# design.net
KiCad netlist of a schematic drawn in Altium Designer
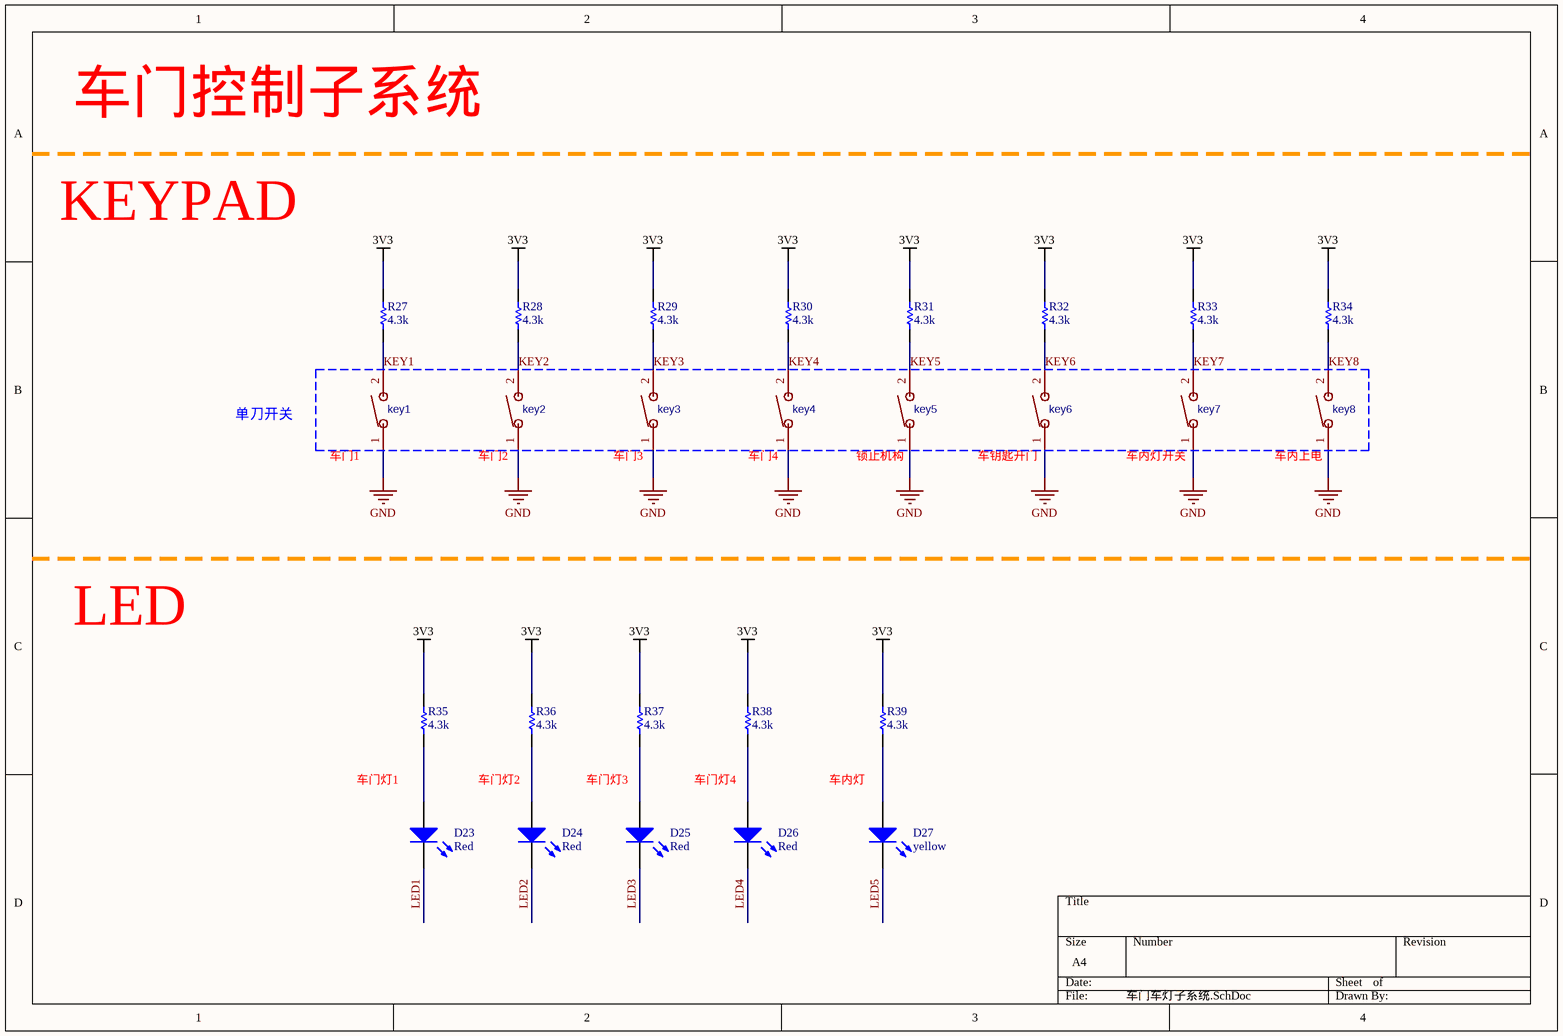
[diagram p0: 车门车灯子系统.SchDoc]

(export (version "E")
  (design (tool "Eeschema 10.0.6"))
  (components
    (comp (ref "D23")
      (value "Red")
      (footprint "LED-TH_L5.0-W2.7-FD")
      (description "红色LED灯")
      (fields (field (name "PART NUMBER") "T_LED_Red_0805"))
      (libsource (lib "Database_Library") (part "LED"))
    )
    (comp (ref "D24")
      (value "Red")
      (footprint "LED-TH_L5.0-W2.7-FD")
      (description "红色LED灯")
      (fields (field (name "PART NUMBER") "T_LED_Red_0805"))
      (libsource (lib "Database_Library") (part "LED"))
    )
    (comp (ref "D25")
      (value "Red")
      (footprint "LED-TH_L5.0-W2.7-FD")
      (description "红色LED灯")
      (fields (field (name "PART NUMBER") "T_LED_Red_0805"))
      (libsource (lib "Database_Library") (part "LED"))
    )
    (comp (ref "D26")
      (value "Red")
      (footprint "LED-TH_L5.0-W2.7-FD")
      (description "红色LED灯")
      (fields (field (name "PART NUMBER") "T_LED_Red_0805"))
      (libsource (lib "Database_Library") (part "LED"))
    )
    (comp (ref "D27")
      (value "yellow")
      (footprint "LED-TH_L5.0-W2.7-FD")
      (description "红色LED灯")
      (fields (field (name "PART NUMBER") "T_LED_Red_0805"))
      (libsource (lib "Database_Library") (part "LED"))
    )
    (comp (ref "key1")
      (value "TSA343G00-250J2")
      (footprint "SW-TH_DEALON_MS-12D19-G2")
      (fields (field (name "BOM_SUPPLIER PART") "C354946") (field (name "CONTRIBUTOR") "LCSC"))
      (libsource (lib "altium-import") (part "root_1_TSA343G00-250J2_"))
    )
    (comp (ref "key2")
      (value "TSA343G00-250J2")
      (footprint "SW-TH_DEALON_MS-12D19-G2")
      (fields (field (name "BOM_SUPPLIER PART") "C354946") (field (name "CONTRIBUTOR") "LCSC"))
      (libsource (lib "altium-import") (part "root_1_TSA343G00-250J2_"))
    )
    (comp (ref "key3")
      (value "TSA343G00-250J2")
      (footprint "SW-TH_DEALON_MS-12D19-G2")
      (fields (field (name "BOM_SUPPLIER PART") "C354946") (field (name "CONTRIBUTOR") "LCSC"))
      (libsource (lib "altium-import") (part "root_1_TSA343G00-250J2_"))
    )
    (comp (ref "key4")
      (value "TSA343G00-250J2")
      (footprint "SW-TH_DEALON_MS-12D19-G2")
      (fields (field (name "BOM_SUPPLIER PART") "C354946") (field (name "CONTRIBUTOR") "LCSC"))
      (libsource (lib "altium-import") (part "root_1_TSA343G00-250J2_"))
    )
    (comp (ref "key5")
      (value "TSA343G00-250J2")
      (footprint "SW-TH_DEALON_MS-12D19-G2")
      (fields (field (name "BOM_SUPPLIER PART") "C354946") (field (name "CONTRIBUTOR") "LCSC"))
      (libsource (lib "altium-import") (part "root_1_TSA343G00-250J2_"))
    )
    (comp (ref "key6")
      (value "TSA343G00-250J2")
      (footprint "SW-TH_DEALON_MS-12D19-G2")
      (fields (field (name "BOM_SUPPLIER PART") "C354946") (field (name "CONTRIBUTOR") "LCSC"))
      (libsource (lib "altium-import") (part "root_1_TSA343G00-250J2_"))
    )
    (comp (ref "key7")
      (value "TSA343G00-250J2")
      (footprint "SW-TH_DEALON_MS-12D19-G2")
      (fields (field (name "BOM_SUPPLIER PART") "C354946") (field (name "CONTRIBUTOR") "LCSC"))
      (libsource (lib "altium-import") (part "root_1_TSA343G00-250J2_"))
    )
    (comp (ref "key8")
      (value "TSA343G00-250J2")
      (footprint "SW-TH_DEALON_MS-12D19-G2")
      (fields (field (name "BOM_SUPPLIER PART") "C354946") (field (name "CONTRIBUTOR") "LCSC"))
      (libsource (lib "altium-import") (part "root_1_TSA343G00-250J2_"))
    )
    (comp (ref "R27")
      (value "4.3k")
      (footprint "0402_R")
      (description "贴片电阻")
      (fields (field (name "PART NUMBER") "T_Res_0603_4.3k_5%_1/10W") (field (name "POWER") "1/10W"))
      (libsource (lib "Database_Library") (part "Res_5%"))
    )
    (comp (ref "R28")
      (value "4.3k")
      (footprint "0402_R")
      (description "贴片电阻")
      (fields (field (name "PART NUMBER") "T_Res_0603_4.3k_5%_1/10W") (field (name "POWER") "1/10W"))
      (libsource (lib "Database_Library") (part "Res_5%"))
    )
    (comp (ref "R29")
      (value "4.3k")
      (footprint "0402_R")
      (description "贴片电阻")
      (fields (field (name "PART NUMBER") "T_Res_0603_4.3k_5%_1/10W") (field (name "POWER") "1/10W"))
      (libsource (lib "Database_Library") (part "Res_5%"))
    )
    (comp (ref "R30")
      (value "4.3k")
      (footprint "0402_R")
      (description "贴片电阻")
      (fields (field (name "PART NUMBER") "T_Res_0603_4.3k_5%_1/10W") (field (name "POWER") "1/10W"))
      (libsource (lib "Database_Library") (part "Res_5%"))
    )
    (comp (ref "R31")
      (value "4.3k")
      (footprint "0402_R")
      (description "贴片电阻")
      (fields (field (name "PART NUMBER") "T_Res_0603_4.3k_5%_1/10W") (field (name "POWER") "1/10W"))
      (libsource (lib "Database_Library") (part "Res_5%"))
    )
    (comp (ref "R32")
      (value "4.3k")
      (footprint "0402_R")
      (description "贴片电阻")
      (fields (field (name "PART NUMBER") "T_Res_0603_4.3k_5%_1/10W") (field (name "POWER") "1/10W"))
      (libsource (lib "Database_Library") (part "Res_5%"))
    )
    (comp (ref "R33")
      (value "4.3k")
      (footprint "0402_R")
      (description "贴片电阻")
      (fields (field (name "PART NUMBER") "T_Res_0603_4.3k_5%_1/10W") (field (name "POWER") "1/10W"))
      (libsource (lib "Database_Library") (part "Res_5%"))
    )
    (comp (ref "R34")
      (value "4.3k")
      (footprint "0402_R")
      (description "贴片电阻")
      (fields (field (name "PART NUMBER") "T_Res_0603_4.3k_5%_1/10W") (field (name "POWER") "1/10W"))
      (libsource (lib "Database_Library") (part "Res_5%"))
    )
    (comp (ref "R35")
      (value "4.3k")
      (footprint "0402_R")
      (description "贴片电阻")
      (fields (field (name "PART NUMBER") "T_Res_0603_4.3k_5%_1/10W") (field (name "POWER") "1/10W"))
      (libsource (lib "Database_Library") (part "Res_5%"))
    )
    (comp (ref "R36")
      (value "4.3k")
      (footprint "0402_R")
      (description "贴片电阻")
      (fields (field (name "PART NUMBER") "T_Res_0603_4.3k_5%_1/10W") (field (name "POWER") "1/10W"))
      (libsource (lib "Database_Library") (part "Res_5%"))
    )
    (comp (ref "R37")
      (value "4.3k")
      (footprint "0402_R")
      (description "贴片电阻")
      (fields (field (name "PART NUMBER") "T_Res_0603_4.3k_5%_1/10W") (field (name "POWER") "1/10W"))
      (libsource (lib "Database_Library") (part "Res_5%"))
    )
    (comp (ref "R38")
      (value "4.3k")
      (footprint "0402_R")
      (description "贴片电阻")
      (fields (field (name "PART NUMBER") "T_Res_0603_4.3k_5%_1/10W") (field (name "POWER") "1/10W"))
      (libsource (lib "Database_Library") (part "Res_5%"))
    )
    (comp (ref "R39")
      (value "4.3k")
      (footprint "0402_R")
      (description "贴片电阻")
      (fields (field (name "PART NUMBER") "T_Res_0603_4.3k_5%_1/10W") (field (name "POWER") "1/10W"))
      (libsource (lib "Database_Library") (part "Res_5%"))
    )
  )
  (nets
    (net (code "1") (name "/KEY1") (class "Default")
      (node (ref "R27") (pin "1") (pinfunction "1_1") (pintype "passive"))
      (node (ref "key1") (pin "2") (pinfunction "2_2") (pintype "passive"))
    )
    (net (code "2") (name "/KEY2") (class "Default")
      (node (ref "R28") (pin "1") (pinfunction "1_1") (pintype "passive"))
      (node (ref "key2") (pin "2") (pinfunction "2_2") (pintype "passive"))
    )
    (net (code "3") (name "/KEY3") (class "Default")
      (node (ref "R29") (pin "1") (pinfunction "1_1") (pintype "passive"))
      (node (ref "key3") (pin "2") (pinfunction "2_2") (pintype "passive"))
    )
    (net (code "4") (name "/KEY4") (class "Default")
      (node (ref "R30") (pin "1") (pinfunction "1_1") (pintype "passive"))
      (node (ref "key4") (pin "2") (pinfunction "2_2") (pintype "passive"))
    )
    (net (code "5") (name "/KEY5") (class "Default")
      (node (ref "R31") (pin "1") (pinfunction "1_1") (pintype "passive"))
      (node (ref "key5") (pin "2") (pinfunction "2_2") (pintype "passive"))
    )
    (net (code "6") (name "/KEY6") (class "Default")
      (node (ref "R32") (pin "1") (pinfunction "1_1") (pintype "passive"))
      (node (ref "key6") (pin "2") (pinfunction "2_2") (pintype "passive"))
    )
    (net (code "7") (name "/KEY7") (class "Default")
      (node (ref "R33") (pin "1") (pinfunction "1_1") (pintype "passive"))
      (node (ref "key7") (pin "2") (pinfunction "2_2") (pintype "passive"))
    )
    (net (code "8") (name "/KEY8") (class "Default")
      (node (ref "R34") (pin "1") (pinfunction "1_1") (pintype "passive"))
      (node (ref "key8") (pin "2") (pinfunction "2_2") (pintype "passive"))
    )
    (net (code "9") (name "/LED1") (class "Default")
      (node (ref "D23") (pin "2") (pinfunction "K_2") (pintype "passive"))
    )
    (net (code "10") (name "/LED2") (class "Default")
      (node (ref "D24") (pin "2") (pinfunction "K_2") (pintype "passive"))
    )
    (net (code "11") (name "/LED3") (class "Default")
      (node (ref "D25") (pin "2") (pinfunction "K_2") (pintype "passive"))
    )
    (net (code "12") (name "/LED4") (class "Default")
      (node (ref "D26") (pin "2") (pinfunction "K_2") (pintype "passive"))
    )
    (net (code "13") (name "/LED5") (class "Default")
      (node (ref "D27") (pin "2") (pinfunction "K_2") (pintype "passive"))
    )
    (net (code "14") (name "3V3") (class "Default")
      (node (ref "R27") (pin "2") (pinfunction "2_2") (pintype "passive"))
      (node (ref "R28") (pin "2") (pinfunction "2_2") (pintype "passive"))
      (node (ref "R29") (pin "2") (pinfunction "2_2") (pintype "passive"))
      (node (ref "R30") (pin "2") (pinfunction "2_2") (pintype "passive"))
      (node (ref "R31") (pin "2") (pinfunction "2_2") (pintype "passive"))
      (node (ref "R32") (pin "2") (pinfunction "2_2") (pintype "passive"))
      (node (ref "R33") (pin "2") (pinfunction "2_2") (pintype "passive"))
      (node (ref "R34") (pin "2") (pinfunction "2_2") (pintype "passive"))
      (node (ref "R35") (pin "2") (pinfunction "2_2") (pintype "passive"))
      (node (ref "R36") (pin "2") (pinfunction "2_2") (pintype "passive"))
      (node (ref "R37") (pin "2") (pinfunction "2_2") (pintype "passive"))
      (node (ref "R38") (pin "2") (pinfunction "2_2") (pintype "passive"))
      (node (ref "R39") (pin "2") (pinfunction "2_2") (pintype "passive"))
    )
    (net (code "15") (name "GND") (class "Default")
      (node (ref "key1") (pin "1") (pinfunction "1_1") (pintype "passive"))
      (node (ref "key2") (pin "1") (pinfunction "1_1") (pintype "passive"))
      (node (ref "key3") (pin "1") (pinfunction "1_1") (pintype "passive"))
      (node (ref "key4") (pin "1") (pinfunction "1_1") (pintype "passive"))
      (node (ref "key5") (pin "1") (pinfunction "1_1") (pintype "passive"))
      (node (ref "key6") (pin "1") (pinfunction "1_1") (pintype "passive"))
      (node (ref "key7") (pin "1") (pinfunction "1_1") (pintype "passive"))
      (node (ref "key8") (pin "1") (pinfunction "1_1") (pintype "passive"))
    )
    (net (code "16") (name "Net-(D23-A)") (class "Default")
      (node (ref "D23") (pin "1") (pinfunction "A_1") (pintype "passive"))
      (node (ref "R35") (pin "1") (pinfunction "1_1") (pintype "passive"))
    )
    (net (code "17") (name "Net-(D24-A)") (class "Default")
      (node (ref "D24") (pin "1") (pinfunction "A_1") (pintype "passive"))
      (node (ref "R36") (pin "1") (pinfunction "1_1") (pintype "passive"))
    )
    (net (code "18") (name "Net-(D25-A)") (class "Default")
      (node (ref "D25") (pin "1") (pinfunction "A_1") (pintype "passive"))
      (node (ref "R37") (pin "1") (pinfunction "1_1") (pintype "passive"))
    )
    (net (code "19") (name "Net-(D26-A)") (class "Default")
      (node (ref "D26") (pin "1") (pinfunction "A_1") (pintype "passive"))
      (node (ref "R38") (pin "1") (pinfunction "1_1") (pintype "passive"))
    )
    (net (code "20") (name "Net-(D27-A)") (class "Default")
      (node (ref "D27") (pin "1") (pinfunction "A_1") (pintype "passive"))
      (node (ref "R39") (pin "1") (pinfunction "1_1") (pintype "passive"))
    )
  )
)
